# Vers_2_Moppy_Board.net
KiCad netlist of a schematic drawn in EAGLE
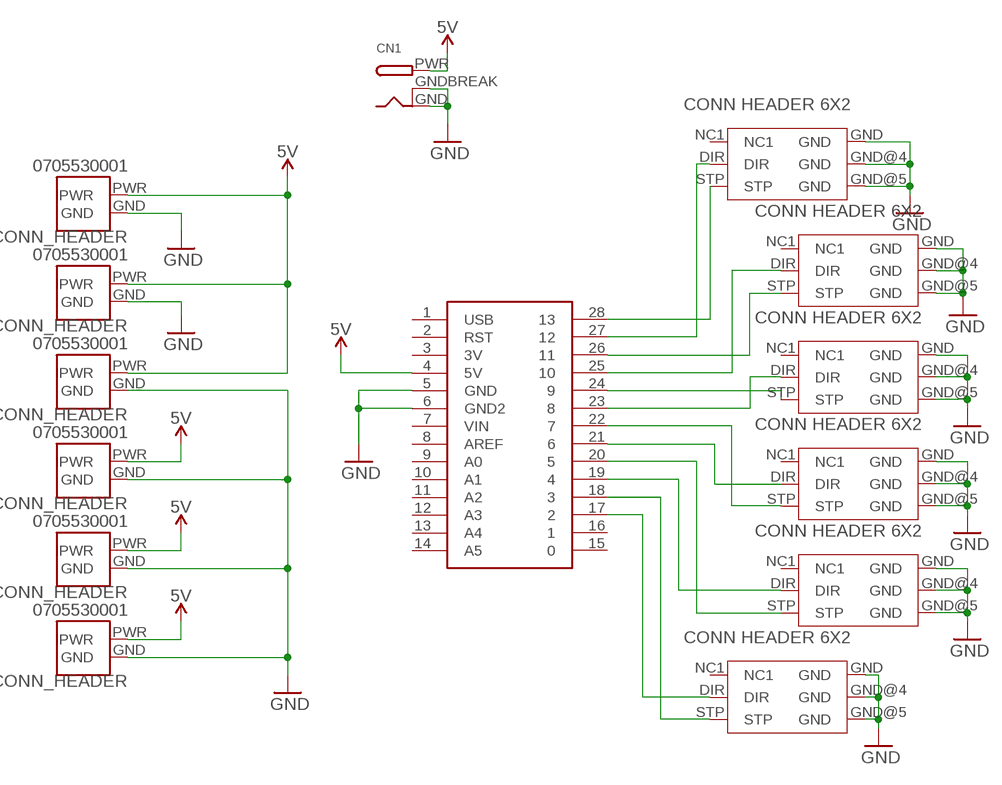
[diagram p0: schematic, sheet 1]

(export (version "E")
  (design (tool "Eeschema 10.0.6"))
  (components
    (comp (ref "CN1")
      (value "DCBARRELPTH")
      (footprint "eagle-import:DCJACK_2MM_PTH")
      (libsource (lib "eagle-import") (part "DCBARRELPTH"))
    )
    (comp (ref "U$1")
      (value "6X2_CONN-HEADER-2.54MM")
      (footprint "eagle-import:6X2_CONN_HEADER_2.54MM")
      (libsource (lib "eagle-import") (part "6X2_CONN-HEADER-2.54MM"))
    )
    (comp (ref "U$2")
      (value "6X2_CONN-HEADER-2.54MM")
      (footprint "eagle-import:6X2_CONN_HEADER_2.54MM")
      (libsource (lib "eagle-import") (part "6X2_CONN-HEADER-2.54MM"))
    )
    (comp (ref "U$3")
      (value "6X2_CONN-HEADER-2.54MM")
      (footprint "eagle-import:6X2_CONN_HEADER_2.54MM")
      (libsource (lib "eagle-import") (part "6X2_CONN-HEADER-2.54MM"))
    )
    (comp (ref "U$4")
      (value "6X2_CONN-HEADER-2.54MM")
      (footprint "eagle-import:6X2_CONN_HEADER_2.54MM")
      (libsource (lib "eagle-import") (part "6X2_CONN-HEADER-2.54MM"))
    )
    (comp (ref "U$5")
      (value "6X2_CONN-HEADER-2.54MM")
      (footprint "eagle-import:6X2_CONN_HEADER_2.54MM")
      (libsource (lib "eagle-import") (part "6X2_CONN-HEADER-2.54MM"))
    )
    (comp (ref "U$6")
      (value "6X2_CONN-HEADER-2.54MM")
      (footprint "eagle-import:6X2_CONN_HEADER_2.54MM")
      (libsource (lib "eagle-import") (part "6X2_CONN-HEADER-2.54MM"))
    )
    (comp (ref "U$8")
      (value "METROMINI")
      (footprint "eagle-import:METROMINI")
      (libsource (lib "eagle-import") (part "METROMINI"))
    )
    (comp (ref "X1")
      (value "0705530001")
      (footprint "eagle-import:MOLEX_0705530001")
      (fields (field (name "DIGI-KEY_PART_NUMBER") "WM4900-ND") (field (name "MF") "Molex"))
      (libsource (lib "eagle-import") (part "0705530001"))
    )
    (comp (ref "X2")
      (value "0705530001")
      (footprint "eagle-import:MOLEX_0705530001")
      (fields (field (name "DIGI-KEY_PART_NUMBER") "WM4900-ND") (field (name "MF") "Molex"))
      (libsource (lib "eagle-import") (part "0705530001"))
    )
    (comp (ref "X3")
      (value "0705530001")
      (footprint "eagle-import:MOLEX_0705530001")
      (fields (field (name "DIGI-KEY_PART_NUMBER") "WM4900-ND") (field (name "MF") "Molex"))
      (libsource (lib "eagle-import") (part "0705530001"))
    )
    (comp (ref "X4")
      (value "0705530001")
      (footprint "eagle-import:MOLEX_0705530001")
      (fields (field (name "DIGI-KEY_PART_NUMBER") "WM4900-ND") (field (name "MF") "Molex"))
      (libsource (lib "eagle-import") (part "0705530001"))
    )
    (comp (ref "X5")
      (value "0705530001")
      (footprint "eagle-import:MOLEX_0705530001")
      (fields (field (name "DIGI-KEY_PART_NUMBER") "WM4900-ND") (field (name "MF") "Molex"))
      (libsource (lib "eagle-import") (part "0705530001"))
    )
    (comp (ref "X6")
      (value "0705530001")
      (footprint "eagle-import:MOLEX_0705530001")
      (fields (field (name "DIGI-KEY_PART_NUMBER") "WM4900-ND") (field (name "MF") "Molex"))
      (libsource (lib "eagle-import") (part "0705530001"))
    )
  )
  (nets
    (net (code "1") (name "5V") (class "Default")
      (node (ref "CN1") (pin "PWR") (pinfunction "PWR_PWR") (pintype "power_in"))
      (node (ref "U$8") (pin "4") (pinfunction "5V_4") (pintype "bidirectional"))
      (node (ref "X1") (pin "PWR") (pinfunction "PWR_PWR") (pintype "passive"))
      (node (ref "X2") (pin "PWR") (pinfunction "PWR_PWR") (pintype "passive"))
      (node (ref "X3") (pin "PWR") (pinfunction "PWR_PWR") (pintype "passive"))
      (node (ref "X4") (pin "PWR") (pinfunction "PWR_PWR") (pintype "passive"))
      (node (ref "X5") (pin "PWR") (pinfunction "PWR_PWR") (pintype "passive"))
      (node (ref "X6") (pin "PWR") (pinfunction "PWR_PWR") (pintype "passive"))
    )
    (net (code "2") (name "GND") (class "Default")
      (node (ref "CN1") (pin "GND") (pinfunction "GND_GND") (pintype "power_in"))
      (node (ref "CN1") (pin "GNDBREAK") (pinfunction "GNDBREAK_GNDBREAK") (pintype "power_in"))
      (node (ref "U$1") (pin "GND") (pinfunction "GND_GND") (pintype "bidirectional"))
      (node (ref "U$1") (pin "GND@4") (pinfunction "GND_GND@4") (pintype "bidirectional"))
      (node (ref "U$1") (pin "GND@5") (pinfunction "GND_GND@5") (pintype "bidirectional"))
      (node (ref "U$2") (pin "GND") (pinfunction "GND_GND") (pintype "bidirectional"))
      (node (ref "U$2") (pin "GND@4") (pinfunction "GND_GND@4") (pintype "bidirectional"))
      (node (ref "U$2") (pin "GND@5") (pinfunction "GND_GND@5") (pintype "bidirectional"))
      (node (ref "U$3") (pin "GND") (pinfunction "GND_GND") (pintype "bidirectional"))
      (node (ref "U$3") (pin "GND@4") (pinfunction "GND_GND@4") (pintype "bidirectional"))
      (node (ref "U$3") (pin "GND@5") (pinfunction "GND_GND@5") (pintype "bidirectional"))
      (node (ref "U$4") (pin "GND") (pinfunction "GND_GND") (pintype "bidirectional"))
      (node (ref "U$4") (pin "GND@4") (pinfunction "GND_GND@4") (pintype "bidirectional"))
      (node (ref "U$4") (pin "GND@5") (pinfunction "GND_GND@5") (pintype "bidirectional"))
      (node (ref "U$5") (pin "GND") (pinfunction "GND_GND") (pintype "bidirectional"))
      (node (ref "U$5") (pin "GND@4") (pinfunction "GND_GND@4") (pintype "bidirectional"))
      (node (ref "U$5") (pin "GND@5") (pinfunction "GND_GND@5") (pintype "bidirectional"))
      (node (ref "U$6") (pin "GND") (pinfunction "GND_GND") (pintype "bidirectional"))
      (node (ref "U$6") (pin "GND@4") (pinfunction "GND_GND@4") (pintype "bidirectional"))
      (node (ref "U$6") (pin "GND@5") (pinfunction "GND_GND@5") (pintype "bidirectional"))
      (node (ref "U$8") (pin "5") (pinfunction "GND_5") (pintype "bidirectional"))
      (node (ref "U$8") (pin "6") (pinfunction "GND2_6") (pintype "bidirectional"))
      (node (ref "X1") (pin "GND") (pinfunction "GND_GND") (pintype "passive"))
      (node (ref "X2") (pin "GND") (pinfunction "GND_GND") (pintype "passive"))
      (node (ref "X3") (pin "GND") (pinfunction "GND_GND") (pintype "passive"))
      (node (ref "X4") (pin "GND") (pinfunction "GND_GND") (pintype "passive"))
      (node (ref "X5") (pin "GND") (pinfunction "GND_GND") (pintype "passive"))
      (node (ref "X6") (pin "GND") (pinfunction "GND_GND") (pintype "passive"))
    )
    (net (code "3") (name "Net-(U$8-2)") (class "Default")
      (node (ref "U$6") (pin "DIR") (pinfunction "DIR_DIR") (pintype "bidirectional"))
      (node (ref "U$8") (pin "17") (pinfunction "2_17") (pintype "bidirectional"))
    )
    (net (code "4") (name "Net-(U$8-3)") (class "Default")
      (node (ref "U$6") (pin "STP") (pinfunction "STP_STP") (pintype "bidirectional"))
      (node (ref "U$8") (pin "18") (pinfunction "3_18") (pintype "bidirectional"))
    )
    (net (code "5") (name "Net-(U$8-4)") (class "Default")
      (node (ref "U$5") (pin "DIR") (pinfunction "DIR_DIR") (pintype "bidirectional"))
      (node (ref "U$8") (pin "19") (pinfunction "4_19") (pintype "bidirectional"))
    )
    (net (code "6") (name "Net-(U$8-5)") (class "Default")
      (node (ref "U$5") (pin "STP") (pinfunction "STP_STP") (pintype "bidirectional"))
      (node (ref "U$8") (pin "20") (pinfunction "5_20") (pintype "bidirectional"))
    )
    (net (code "7") (name "Net-(U$8-6)") (class "Default")
      (node (ref "U$4") (pin "DIR") (pinfunction "DIR_DIR") (pintype "bidirectional"))
      (node (ref "U$8") (pin "21") (pinfunction "6_21") (pintype "bidirectional"))
    )
    (net (code "8") (name "Net-(U$8-7)") (class "Default")
      (node (ref "U$4") (pin "STP") (pinfunction "STP_STP") (pintype "bidirectional"))
      (node (ref "U$8") (pin "22") (pinfunction "7_22") (pintype "bidirectional"))
    )
    (net (code "9") (name "Net-(U$8-8)") (class "Default")
      (node (ref "U$3") (pin "DIR") (pinfunction "DIR_DIR") (pintype "bidirectional"))
      (node (ref "U$8") (pin "23") (pinfunction "8_23") (pintype "bidirectional"))
    )
    (net (code "10") (name "Net-(U$8-9)") (class "Default")
      (node (ref "U$3") (pin "STP") (pinfunction "STP_STP") (pintype "bidirectional"))
      (node (ref "U$8") (pin "24") (pinfunction "9_24") (pintype "bidirectional"))
    )
    (net (code "11") (name "Net-(U$8-10)") (class "Default")
      (node (ref "U$2") (pin "DIR") (pinfunction "DIR_DIR") (pintype "bidirectional"))
      (node (ref "U$8") (pin "25") (pinfunction "10_25") (pintype "bidirectional"))
    )
    (net (code "12") (name "Net-(U$8-11)") (class "Default")
      (node (ref "U$2") (pin "STP") (pinfunction "STP_STP") (pintype "bidirectional"))
      (node (ref "U$8") (pin "26") (pinfunction "11_26") (pintype "bidirectional"))
    )
    (net (code "13") (name "Net-(U$8-12)") (class "Default")
      (node (ref "U$1") (pin "DIR") (pinfunction "DIR_DIR") (pintype "bidirectional"))
      (node (ref "U$8") (pin "27") (pinfunction "12_27") (pintype "bidirectional"))
    )
    (net (code "14") (name "Net-(U$8-13)") (class "Default")
      (node (ref "U$1") (pin "STP") (pinfunction "STP_STP") (pintype "bidirectional"))
      (node (ref "U$8") (pin "28") (pinfunction "13_28") (pintype "bidirectional"))
    )
    (net (code "15") (name "unconnected-(U$1-PadNC1)") (class "Default")
      (node (ref "U$1") (pin "NC1") (pinfunction "NC1_NC1") (pintype "bidirectional"))
    )
    (net (code "16") (name "unconnected-(U$2-PadNC1)") (class "Default")
      (node (ref "U$2") (pin "NC1") (pinfunction "NC1_NC1") (pintype "bidirectional"))
    )
    (net (code "17") (name "unconnected-(U$3-PadNC1)") (class "Default")
      (node (ref "U$3") (pin "NC1") (pinfunction "NC1_NC1") (pintype "bidirectional"))
    )
    (net (code "18") (name "unconnected-(U$4-PadNC1)") (class "Default")
      (node (ref "U$4") (pin "NC1") (pinfunction "NC1_NC1") (pintype "bidirectional"))
    )
    (net (code "19") (name "unconnected-(U$5-PadNC1)") (class "Default")
      (node (ref "U$5") (pin "NC1") (pinfunction "NC1_NC1") (pintype "bidirectional"))
    )
    (net (code "20") (name "unconnected-(U$6-PadNC1)") (class "Default")
      (node (ref "U$6") (pin "NC1") (pinfunction "NC1_NC1") (pintype "bidirectional"))
    )
    (net (code "21") (name "unconnected-(U$8-0-Pad15)") (class "Default")
      (node (ref "U$8") (pin "15") (pinfunction "0_15") (pintype "bidirectional"))
    )
    (net (code "22") (name "unconnected-(U$8-1-Pad16)") (class "Default")
      (node (ref "U$8") (pin "16") (pinfunction "1_16") (pintype "bidirectional"))
    )
    (net (code "23") (name "unconnected-(U$8-3V-Pad3)") (class "Default")
      (node (ref "U$8") (pin "3") (pinfunction "3V_3") (pintype "bidirectional"))
    )
    (net (code "24") (name "unconnected-(U$8-A0-Pad9)") (class "Default")
      (node (ref "U$8") (pin "9") (pinfunction "A0_9") (pintype "bidirectional"))
    )
    (net (code "25") (name "unconnected-(U$8-A1-Pad10)") (class "Default")
      (node (ref "U$8") (pin "10") (pinfunction "A1_10") (pintype "bidirectional"))
    )
    (net (code "26") (name "unconnected-(U$8-A2-Pad11)") (class "Default")
      (node (ref "U$8") (pin "11") (pinfunction "A2_11") (pintype "bidirectional"))
    )
    (net (code "27") (name "unconnected-(U$8-A3-Pad12)") (class "Default")
      (node (ref "U$8") (pin "12") (pinfunction "A3_12") (pintype "bidirectional"))
    )
    (net (code "28") (name "unconnected-(U$8-A4-Pad13)") (class "Default")
      (node (ref "U$8") (pin "13") (pinfunction "A4_13") (pintype "bidirectional"))
    )
    (net (code "29") (name "unconnected-(U$8-A5-Pad14)") (class "Default")
      (node (ref "U$8") (pin "14") (pinfunction "A5_14") (pintype "bidirectional"))
    )
    (net (code "30") (name "unconnected-(U$8-AREF-Pad8)") (class "Default")
      (node (ref "U$8") (pin "8") (pinfunction "AREF_8") (pintype "bidirectional"))
    )
    (net (code "31") (name "unconnected-(U$8-RST-Pad2)") (class "Default")
      (node (ref "U$8") (pin "2") (pinfunction "RST_2") (pintype "bidirectional"))
    )
    (net (code "32") (name "unconnected-(U$8-USB-Pad1)") (class "Default")
      (node (ref "U$8") (pin "1") (pinfunction "USB_1") (pintype "bidirectional"))
    )
    (net (code "33") (name "unconnected-(U$8-VIN-Pad7)") (class "Default")
      (node (ref "U$8") (pin "7") (pinfunction "VIN_7") (pintype "bidirectional"))
    )
  )
)
